# VIA_MOTORS.net
KiCad netlist of a schematic drawn in Altium Designer
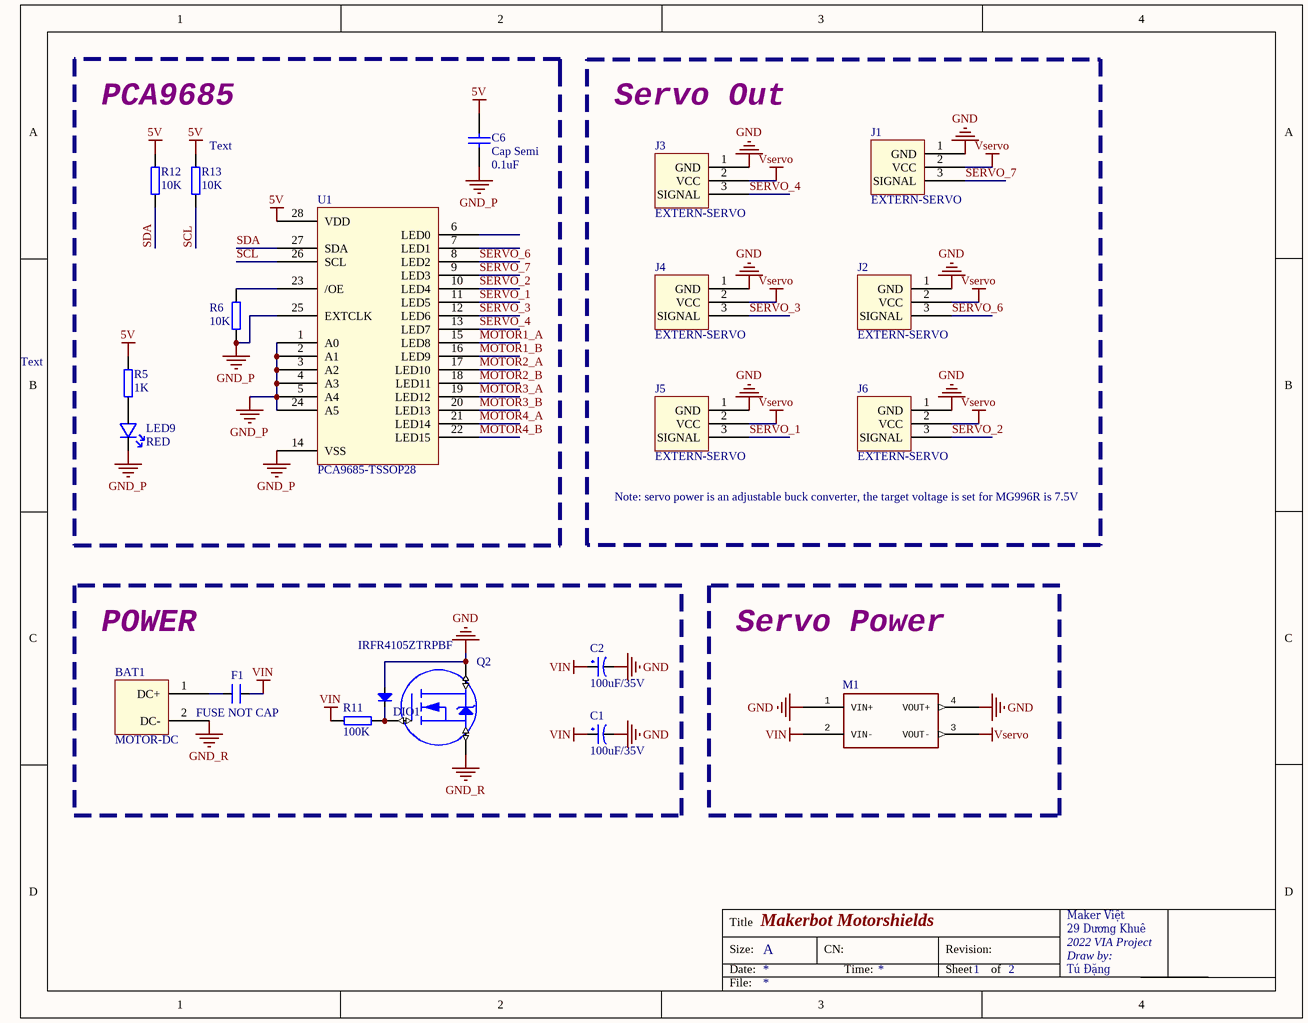
[diagram p0: VIA_MOTORS.SchDoc]

(export (version "E")
  (design (tool "Eeschema 10.0.6"))
  (components
    (comp (ref "BAT1")
      (value "MOTOR-DC")
      (footprint "CON2-5.08DC")
      (libsource (lib "RASHBERRY_EXTERN") (part "MOTOR-DC"))
    )
    (comp (ref "C1")
      (value "100uF/35V")
      (footprint "CP1.5/3.4")
      (description "Cap 100uF/35V - 470uF/16V")
      (libsource (lib "My Library") (part "CP3"))
    )
    (comp (ref "C2")
      (value "100uF/35V")
      (footprint "CP1.5/3.4")
      (description "Cap 100uF/35V - 470uF/16V")
      (libsource (lib "My Library") (part "CP3"))
    )
    (comp (ref "C6")
      (value "Cap Semi")
      (footprint "SMT0603")
      (description "CAP SM 0603 X7R 1uF 10%")
      (fields (field (name "TOLERANCE") "±10%") (field (name "ALTIUM_VALUE") "0.1uF"))
      (libsource (lib "electronpowered") (part "CAP-SM-0603-X7R-1uF"))
    )
    (comp (ref "DIO1")
      (value "Diode SMD")
      (footprint "DIO-SMD-123")
      (description "Default Diode")
      (fields (field (name "PUBLISHER") "Altium Limited"))
      (libsource (lib "My Library") (part "Diode SMD"))
    )
    (comp (ref "F1")
      (value "FUSE NOT CAP")
      (footprint "CN2")
      (description "Cap np 104 => 105pF")
      (libsource (lib "My Library") (part "CN2"))
    )
    (comp (ref "J1")
      (value "EXTERN-SERVO")
      (footprint "JP3H")
      (libsource (lib "RASHBERRY_EXTERN") (part "EXTERN-SERVO"))
    )
    (comp (ref "J2")
      (value "EXTERN-SERVO")
      (footprint "JP3H")
      (libsource (lib "RASHBERRY_EXTERN") (part "EXTERN-SERVO"))
    )
    (comp (ref "J3")
      (value "EXTERN-SERVO")
      (footprint "JP3H")
      (libsource (lib "RASHBERRY_EXTERN") (part "EXTERN-SERVO"))
    )
    (comp (ref "J4")
      (value "EXTERN-SERVO")
      (footprint "JP3H")
      (libsource (lib "RASHBERRY_EXTERN") (part "EXTERN-SERVO"))
    )
    (comp (ref "J5")
      (value "EXTERN-SERVO")
      (footprint "JP3H")
      (libsource (lib "RASHBERRY_EXTERN") (part "EXTERN-SERVO"))
    )
    (comp (ref "J6")
      (value "EXTERN-SERVO")
      (footprint "JP3H")
      (libsource (lib "RASHBERRY_EXTERN") (part "EXTERN-SERVO"))
    )
    (comp (ref "LED9")
      (value "RED")
      (footprint "SMT0603P")
      (description "LED SM 0603 RED 1V95 FWD VOLTAGE")
      (libsource (lib "electronpowered") (part "LNJ237W82RA"))
    )
    (comp (ref "M1")
      (value "MP1584-dc-brick-pcb Step down Input: 4.5V - 28V Ouput 0.8V - 25V max. 3A Cheap on ebay")
      (footprint "MP1584 MODULE - duplicate")
      (libsource (lib "MP1584-dc-brick") (part "MP1584"))
    )
    (comp (ref "Q2")
      (value "IRFR4105ZTRPBF")
      (footprint "TO252-3:TO252-3")
      (description "RoHS Compliant ¦ Industry-leading quality ¦ Fast Switching ¦ 175C Operating Temperature")
      (fields
        (field (name "DIGI-KEY_PART_NUMBER") "IRFR4105ZTRPBFCT-ND")
        (field (name "MF") "Infineon Technologies")
      )
      (libsource (lib "IRFR4105ZTRPBF") (part "IRFR4105ZTRPBF"))
    )
    (comp (ref "R5")
      (value "1K")
      (footprint "SMT0603")
      (description "RES SM 0603 1K")
      (fields (field (name "Comment") "Resistor"))
      (libsource (lib "electronpowered") (part "RES-SM-0603-1K"))
    )
    (comp (ref "R6")
      (value "10K")
      (footprint "SMT0603")
      (description "RES SM 0603 10K")
      (fields (field (name "Comment") "Resistor"))
      (libsource (lib "electronpowered") (part "RES-SM-0603-10K"))
    )
    (comp (ref "R11")
      (value "100K")
      (footprint "SMT0603")
      (description "RES SM 0603 100K")
      (fields (field (name "Comment") "Resistor"))
      (libsource (lib "electronpowered") (part "RES-SM-0603-100K"))
    )
    (comp (ref "R12")
      (value "10K")
      (footprint "SMT0603")
      (description "RES SM 0603 10K")
      (fields (field (name "Comment") "Resistor"))
      (libsource (lib "electronpowered") (part "RES-SM-0603-10K"))
    )
    (comp (ref "R13")
      (value "10K")
      (footprint "SMT0603")
      (description "RES SM 0603 10K")
      (fields (field (name "Comment") "Resistor"))
      (libsource (lib "electronpowered") (part "RES-SM-0603-10K"))
    )
    (comp (ref "U1")
      (value "PCA9685-TSSOP28")
      (footprint "TSSOP28-SMD")
      (libsource (lib "RASHBERRY_EXTERN") (part "PCA9685-TSSOP28"))
    )
  )
  (nets
    (net (code "1") (name "/MOTOR1_A") (class "Default")
      (node (ref "U1") (pin "15") (pinfunction "LED8_15") (pintype "passive"))
    )
    (net (code "2") (name "/MOTOR1_B") (class "Default")
      (node (ref "U1") (pin "16") (pinfunction "LED9_16") (pintype "passive"))
    )
    (net (code "3") (name "/MOTOR2_A") (class "Default")
      (node (ref "U1") (pin "17") (pinfunction "LED10_17") (pintype "passive"))
    )
    (net (code "4") (name "/MOTOR2_B") (class "Default")
      (node (ref "U1") (pin "18") (pinfunction "LED11_18") (pintype "passive"))
    )
    (net (code "5") (name "/MOTOR3_A") (class "Default")
      (node (ref "U1") (pin "19") (pinfunction "LED12_19") (pintype "passive"))
    )
    (net (code "6") (name "/MOTOR3_B") (class "Default")
      (node (ref "U1") (pin "20") (pinfunction "LED13_20") (pintype "passive"))
    )
    (net (code "7") (name "/MOTOR4_A") (class "Default")
      (node (ref "U1") (pin "21") (pinfunction "LED14_21") (pintype "passive"))
    )
    (net (code "8") (name "/MOTOR4_B") (class "Default")
      (node (ref "U1") (pin "22") (pinfunction "LED15_22") (pintype "passive"))
    )
    (net (code "9") (name "/SCL") (class "Default")
      (node (ref "R13") (pin "1") (pinfunction "1_1") (pintype "passive"))
      (node (ref "U1") (pin "26") (pinfunction "SCL_26") (pintype "passive"))
    )
    (net (code "10") (name "/SDA") (class "Default")
      (node (ref "R12") (pin "1") (pinfunction "1_1") (pintype "passive"))
      (node (ref "U1") (pin "27") (pinfunction "SDA_27") (pintype "passive"))
    )
    (net (code "11") (name "/SERVO_1") (class "Default")
      (node (ref "J5") (pin "3") (pinfunction "SIGNAL_3") (pintype "passive"))
      (node (ref "U1") (pin "11") (pinfunction "LED5_11") (pintype "passive"))
    )
    (net (code "12") (name "/SERVO_2") (class "Default")
      (node (ref "J6") (pin "3") (pinfunction "SIGNAL_3") (pintype "passive"))
      (node (ref "U1") (pin "10") (pinfunction "LED4_10") (pintype "passive"))
    )
    (net (code "13") (name "/SERVO_3") (class "Default")
      (node (ref "J4") (pin "3") (pinfunction "SIGNAL_3") (pintype "passive"))
      (node (ref "U1") (pin "12") (pinfunction "LED6_12") (pintype "passive"))
    )
    (net (code "14") (name "/SERVO_4") (class "Default")
      (node (ref "J3") (pin "3") (pinfunction "SIGNAL_3") (pintype "passive"))
      (node (ref "U1") (pin "13") (pinfunction "LED7_13") (pintype "passive"))
    )
    (net (code "15") (name "/SERVO_6") (class "Default")
      (node (ref "J2") (pin "3") (pinfunction "SIGNAL_3") (pintype "passive"))
      (node (ref "U1") (pin "8") (pinfunction "LED2_8") (pintype "passive"))
    )
    (net (code "16") (name "/SERVO_7") (class "Default")
      (node (ref "J1") (pin "3") (pinfunction "SIGNAL_3") (pintype "passive"))
      (node (ref "U1") (pin "9") (pinfunction "LED3_9") (pintype "passive"))
    )
    (net (code "17") (name "5V") (class "Default")
      (node (ref "C6") (pin "2") (pinfunction "2_2") (pintype "passive"))
      (node (ref "R12") (pin "2") (pinfunction "2_2") (pintype "passive"))
      (node (ref "R13") (pin "2") (pinfunction "2_2") (pintype "passive"))
      (node (ref "R5") (pin "2") (pinfunction "2_2") (pintype "passive"))
      (node (ref "U1") (pin "28") (pinfunction "VDD_28") (pintype "passive"))
    )
    (net (code "18") (name "GND") (class "Default")
      (node (ref "C1") (pin "2") (pinfunction "2_2") (pintype "passive"))
      (node (ref "C2") (pin "2") (pinfunction "2_2") (pintype "passive"))
      (node (ref "DIO1") (pin "1") (pinfunction "A_1") (pintype "passive"))
      (node (ref "J1") (pin "1") (pinfunction "GND_1") (pintype "passive"))
      (node (ref "J2") (pin "1") (pinfunction "GND_1") (pintype "passive"))
      (node (ref "J3") (pin "1") (pinfunction "GND_1") (pintype "passive"))
      (node (ref "J4") (pin "1") (pinfunction "GND_1") (pintype "passive"))
      (node (ref "J5") (pin "1") (pinfunction "GND_1") (pintype "passive"))
      (node (ref "J6") (pin "1") (pinfunction "GND_1") (pintype "passive"))
      (node (ref "M1") (pin "1") (pinfunction "VIN+_1") (pintype "passive"))
      (node (ref "M1") (pin "4") (pinfunction "VOUT+_4") (pintype "output"))
      (node (ref "Q2") (pin "2") (pinfunction "D@1_2") (pintype "bidirectional"))
    )
    (net (code "19") (name "GND_P") (class "Default")
      (node (ref "C6") (pin "1") (pinfunction "1_1") (pintype "passive"))
      (node (ref "LED9") (pin "2") (pinfunction "2_2") (pintype "passive"))
      (node (ref "R6") (pin "1") (pinfunction "1_1") (pintype "passive"))
      (node (ref "U1") (pin "1") (pinfunction "A0_1") (pintype "passive"))
      (node (ref "U1") (pin "14") (pinfunction "VSS_14") (pintype "passive"))
      (node (ref "U1") (pin "2") (pinfunction "A1_2") (pintype "passive"))
      (node (ref "U1") (pin "24") (pinfunction "A5_24") (pintype "passive"))
      (node (ref "U1") (pin "25") (pinfunction "EXTCLK_25") (pintype "passive"))
      (node (ref "U1") (pin "3") (pinfunction "A2_3") (pintype "passive"))
      (node (ref "U1") (pin "4") (pinfunction "A3_4") (pintype "passive"))
      (node (ref "U1") (pin "5") (pinfunction "A4_5") (pintype "passive"))
    )
    (net (code "20") (name "GND_R") (class "Default")
      (node (ref "BAT1") (pin "2") (pinfunction "DC-_2") (pintype "passive"))
      (node (ref "Q2") (pin "3") (pinfunction "S_3") (pintype "bidirectional"))
    )
    (net (code "21") (name "Net-(BAT1-DC+)") (class "Default")
      (node (ref "BAT1") (pin "1") (pinfunction "DC+_1") (pintype "passive"))
      (node (ref "F1") (pin "1") (pinfunction "1_1") (pintype "passive"))
    )
    (net (code "22") (name "Net-(DIO1-K)") (class "Default")
      (node (ref "DIO1") (pin "2") (pinfunction "K_2") (pintype "passive"))
      (node (ref "Q2") (pin "1") (pinfunction "G_1") (pintype "bidirectional"))
      (node (ref "R11") (pin "1") (pinfunction "1_1") (pintype "passive"))
    )
    (net (code "23") (name "Net-(LED9-Pad1)") (class "Default")
      (node (ref "LED9") (pin "1") (pinfunction "1_1") (pintype "passive"))
      (node (ref "R5") (pin "1") (pinfunction "1_1") (pintype "passive"))
    )
    (net (code "24") (name "Net-(U1-{slash}OE)") (class "Default")
      (node (ref "R6") (pin "2") (pinfunction "2_2") (pintype "passive"))
      (node (ref "U1") (pin "23") (pinfunction "/OE_23") (pintype "passive"))
    )
    (net (code "25") (name "VIN") (class "Default")
      (node (ref "C1") (pin "1") (pinfunction "1_1") (pintype "passive"))
      (node (ref "C2") (pin "1") (pinfunction "1_1") (pintype "passive"))
      (node (ref "F1") (pin "2") (pinfunction "2_2") (pintype "passive"))
      (node (ref "M1") (pin "2") (pinfunction "VIN-_2") (pintype "passive"))
      (node (ref "R11") (pin "2") (pinfunction "2_2") (pintype "passive"))
    )
    (net (code "26") (name "Vservo") (class "Default")
      (node (ref "J1") (pin "2") (pinfunction "VCC_2") (pintype "passive"))
      (node (ref "J2") (pin "2") (pinfunction "VCC_2") (pintype "passive"))
      (node (ref "J3") (pin "2") (pinfunction "VCC_2") (pintype "passive"))
      (node (ref "J4") (pin "2") (pinfunction "VCC_2") (pintype "passive"))
      (node (ref "J5") (pin "2") (pinfunction "VCC_2") (pintype "passive"))
      (node (ref "J6") (pin "2") (pinfunction "VCC_2") (pintype "passive"))
      (node (ref "M1") (pin "3") (pinfunction "VOUT-_3") (pintype "output"))
    )
    (net (code "27") (name "unconnected-(Q2-D@2-PadPAD)") (class "Default")
      (node (ref "Q2") (pin "PAD") (pinfunction "D@2_PAD") (pintype "bidirectional"))
    )
    (net (code "28") (name "unconnected-(U1-LED0-Pad6)") (class "Default")
      (node (ref "U1") (pin "6") (pinfunction "LED0_6") (pintype "passive"))
    )
    (net (code "29") (name "unconnected-(U1-LED1-Pad7)") (class "Default")
      (node (ref "U1") (pin "7") (pinfunction "LED1_7") (pintype "passive"))
    )
  )
)
